# sch.net
KiCad netlist of a schematic drawn in Altium Designer
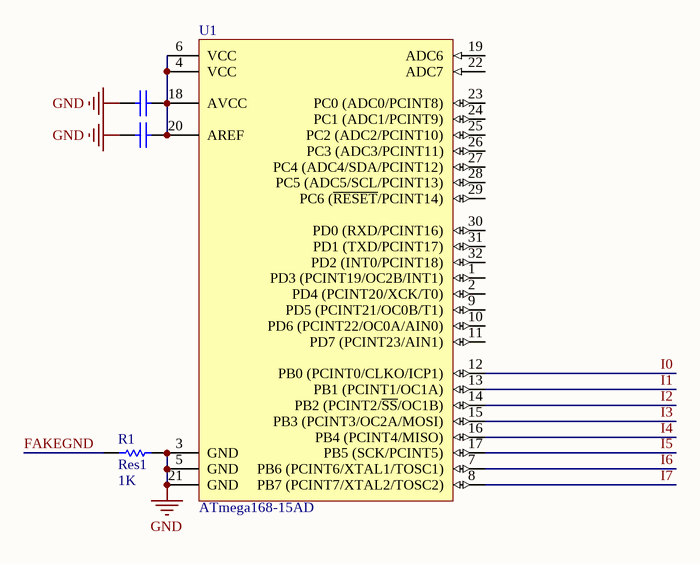
[diagram p0: sch.SchDoc]

(export (version "E")
  (design (tool "Eeschema 10.0.6"))
  (components
    (comp (ref "C1")
      (value "Cap")
      (footprint "0603x")
      (description "Capacitor")
      (fields (field (name "PUBLISHER") "Altium Limited"))
      (libsource (lib "Miscellaneous Devices") (part "Cap"))
    )
    (comp (ref "C2")
      (value "Cap")
      (footprint "0603x")
      (description "Capacitor")
      (fields (field (name "PUBLISHER") "Altium Limited"))
      (libsource (lib "Miscellaneous Devices") (part "Cap"))
    )
    (comp (ref "R1")
      (value "Res1")
      (footprint "0603x")
      (description "Resistor")
      (fields (field (name "ALTIUM_VALUE") "1K") (field (name "PUBLISHER") "Altium Limited"))
      (libsource (lib "Miscellaneous Devices") (part "Res1"))
    )
    (comp (ref "U1")
      (value "ATmega168-15AD")
      (footprint "32MA_N")
      (fields (field (name "PUBLISHER") "Altium Limited"))
      (libsource (lib "Atmel Microcontroller 8-Bit Automotive AVR") (part "ATmega168-15AD"))
    )
  )
  (nets
    (net (code "1") (name "/FAKEGND") (class "Default")
      (node (ref "R1") (pin "1") (pinfunction "1_1") (pintype "passive"))
    )
    (net (code "2") (name "/I0") (class "Default")
      (node (ref "U1") (pin "12") (pinfunction "PB0_(PCINT0/CLKO/ICP1)_12") (pintype "bidirectional"))
    )
    (net (code "3") (name "/I1") (class "Default")
      (node (ref "U1") (pin "13") (pinfunction "PB1_(PCINT1/OC1A)_13") (pintype "bidirectional"))
    )
    (net (code "4") (name "/I2") (class "Default")
      (node (ref "U1") (pin "14") (pinfunction "PB2_(PCINT2/~{SS}/OC1B)_14") (pintype "bidirectional"))
    )
    (net (code "5") (name "/I3") (class "Default")
      (node (ref "U1") (pin "15") (pinfunction "PB3_(PCINT3/OC2A/MOSI)_15") (pintype "bidirectional"))
    )
    (net (code "6") (name "/I4") (class "Default")
      (node (ref "U1") (pin "16") (pinfunction "PB4_(PCINT4/MISO)_16") (pintype "bidirectional"))
    )
    (net (code "7") (name "/I5") (class "Default")
      (node (ref "U1") (pin "17") (pinfunction "PB5_(SCK/PCINT5)_17") (pintype "bidirectional"))
    )
    (net (code "8") (name "/I6") (class "Default")
      (node (ref "U1") (pin "7") (pinfunction "PB6_(PCINT6/XTAL1/TOSC1)_7") (pintype "bidirectional"))
    )
    (net (code "9") (name "/I7") (class "Default")
      (node (ref "U1") (pin "8") (pinfunction "PB7_(PCINT7/XTAL2/TOSC2)_8") (pintype "bidirectional"))
    )
    (net (code "10") (name "GND") (class "Default")
      (node (ref "C1") (pin "2") (pinfunction "2_2") (pintype "passive"))
      (node (ref "C2") (pin "2") (pinfunction "2_2") (pintype "passive"))
      (node (ref "R1") (pin "2") (pinfunction "2_2") (pintype "passive"))
      (node (ref "U1") (pin "21") (pinfunction "GND_21") (pintype "power_in"))
      (node (ref "U1") (pin "3") (pinfunction "GND_3") (pintype "power_in"))
      (node (ref "U1") (pin "5") (pinfunction "GND_5") (pintype "power_in"))
    )
    (net (code "11") (name "Net-(U1-AREF)") (class "Default")
      (node (ref "C1") (pin "1") (pinfunction "1_1") (pintype "passive"))
      (node (ref "C2") (pin "1") (pinfunction "1_1") (pintype "passive"))
      (node (ref "U1") (pin "18") (pinfunction "AVCC_18") (pintype "power_in"))
      (node (ref "U1") (pin "20") (pinfunction "AREF_20") (pintype "passive"))
      (node (ref "U1") (pin "4") (pinfunction "VCC_4") (pintype "power_in"))
      (node (ref "U1") (pin "6") (pinfunction "VCC_6") (pintype "power_in"))
    )
    (net (code "12") (name "unconnected-(U1-ADC6-Pad19)") (class "Default")
      (node (ref "U1") (pin "19") (pinfunction "ADC6_19") (pintype "input"))
    )
    (net (code "13") (name "unconnected-(U1-ADC7-Pad22)") (class "Default")
      (node (ref "U1") (pin "22") (pinfunction "ADC7_22") (pintype "input"))
    )
    (net (code "14") (name "unconnected-(U1-PC0_(ADC0{slash}PCINT8)-Pad23)") (class "Default")
      (node (ref "U1") (pin "23") (pinfunction "PC0_(ADC0/PCINT8)_23") (pintype "bidirectional"))
    )
    (net (code "15") (name "unconnected-(U1-PC1_(ADC1{slash}PCINT9)-Pad24)") (class "Default")
      (node (ref "U1") (pin "24") (pinfunction "PC1_(ADC1/PCINT9)_24") (pintype "bidirectional"))
    )
    (net (code "16") (name "unconnected-(U1-PC2_(ADC2{slash}PCINT10)-Pad25)") (class "Default")
      (node (ref "U1") (pin "25") (pinfunction "PC2_(ADC2/PCINT10)_25") (pintype "bidirectional"))
    )
    (net (code "17") (name "unconnected-(U1-PC3_(ADC3{slash}PCINT11)-Pad26)") (class "Default")
      (node (ref "U1") (pin "26") (pinfunction "PC3_(ADC3/PCINT11)_26") (pintype "bidirectional"))
    )
    (net (code "18") (name "unconnected-(U1-PC4_(ADC4{slash}SDA{slash}PCINT12)-Pad27)") (class "Default")
      (node (ref "U1") (pin "27") (pinfunction "PC4_(ADC4/SDA/PCINT12)_27") (pintype "bidirectional"))
    )
    (net (code "19") (name "unconnected-(U1-PC5_(ADC5{slash}SCL{slash}PCINT13)-Pad28)") (class "Default")
      (node (ref "U1") (pin "28") (pinfunction "PC5_(ADC5/SCL/PCINT13)_28") (pintype "bidirectional"))
    )
    (net (code "20") (name "unconnected-(U1-PC6_(~{RESET}{slash}PCINT14)-Pad29)") (class "Default")
      (node (ref "U1") (pin "29") (pinfunction "PC6_(~{RESET}/PCINT14)_29") (pintype "bidirectional"))
    )
    (net (code "21") (name "unconnected-(U1-PD0_(RXD{slash}PCINT16)-Pad30)") (class "Default")
      (node (ref "U1") (pin "30") (pinfunction "PD0_(RXD/PCINT16)_30") (pintype "bidirectional"))
    )
    (net (code "22") (name "unconnected-(U1-PD1_(TXD{slash}PCINT17)-Pad31)") (class "Default")
      (node (ref "U1") (pin "31") (pinfunction "PD1_(TXD/PCINT17)_31") (pintype "bidirectional"))
    )
    (net (code "23") (name "unconnected-(U1-PD2_(INT0{slash}PCINT18)-Pad32)") (class "Default")
      (node (ref "U1") (pin "32") (pinfunction "PD2_(INT0/PCINT18)_32") (pintype "bidirectional"))
    )
    (net (code "24") (name "unconnected-(U1-PD3_(PCINT19{slash}OC2B{slash}INT1)-Pad1)") (class "Default")
      (node (ref "U1") (pin "1") (pinfunction "PD3_(PCINT19/OC2B/INT1)_1") (pintype "bidirectional"))
    )
    (net (code "25") (name "unconnected-(U1-PD4_(PCINT20{slash}XCK{slash}T0)-Pad2)") (class "Default")
      (node (ref "U1") (pin "2") (pinfunction "PD4_(PCINT20/XCK/T0)_2") (pintype "bidirectional"))
    )
    (net (code "26") (name "unconnected-(U1-PD5_(PCINT21{slash}OC0B{slash}T1)-Pad9)") (class "Default")
      (node (ref "U1") (pin "9") (pinfunction "PD5_(PCINT21/OC0B/T1)_9") (pintype "bidirectional"))
    )
    (net (code "27") (name "unconnected-(U1-PD6_(PCINT22{slash}OC0A{slash}AIN0)-Pad10)") (class "Default")
      (node (ref "U1") (pin "10") (pinfunction "PD6_(PCINT22/OC0A/AIN0)_10") (pintype "bidirectional"))
    )
    (net (code "28") (name "unconnected-(U1-PD7_(PCINT23{slash}AIN1)-Pad11)") (class "Default")
      (node (ref "U1") (pin "11") (pinfunction "PD7_(PCINT23/AIN1)_11") (pintype "bidirectional"))
    )
  )
)
